# boost-converter.net
KiCad netlist of a schematic drawn in Altium Designer
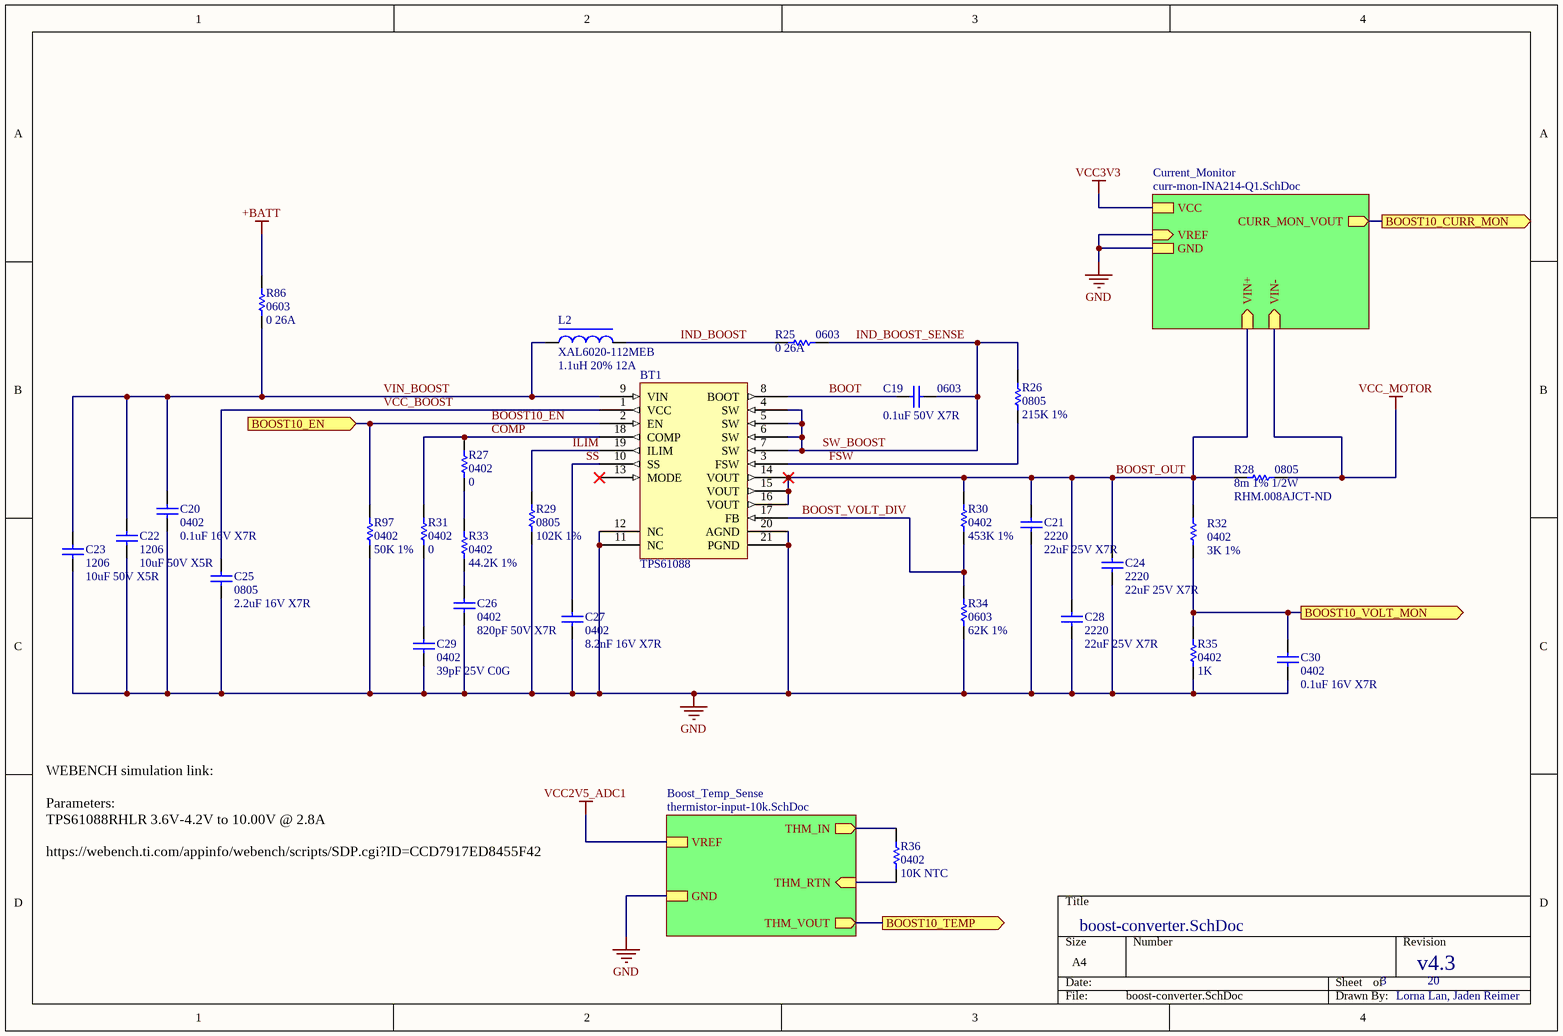
[diagram p0: boost-converter.SchDoc]

(export (version "E")
  (design (tool "Eeschema 10.0.6"))
  (components
    (comp (ref "BT1")
      (value "TPS61088")
      (footprint "QFN50P450X350X100-21N")
      (description "Boost converter")
      (libsource (lib "EPS") (part "TPS61088"))
    )
    (comp (ref "C19")
      (value "0603")
      (footprint "CAP0603R")
      (description "0603 capacitor")
      (fields (field (name "ALTIUM_VALUE") "0.1uF 50V X7R"))
      (libsource (lib "CAP0603") (part "CAP0603"))
    )
    (comp (ref "C20")
      (value "0402")
      (footprint "CAP0402R")
      (description "0402 capacitor")
      (fields (field (name "ALTIUM_VALUE") "0.1uF 16V X7R"))
      (libsource (lib "heron-general") (part "CAP0402"))
    )
    (comp (ref "C21")
      (value "2220")
      (footprint "CAP2220")
      (description "Ceramic Capacitor 2220 (5750 Metric)")
      (fields (field (name "ALTIUM_VALUE") "22uF 25V X7R"))
      (libsource (lib "CAP2220") (part "CAP2220"))
    )
    (comp (ref "C22")
      (value "1206")
      (footprint "CAP1206R")
      (description "1206 capacitor")
      (fields (field (name "ALTIUM_VALUE") "10uF 50V X5R"))
      (libsource (lib "CAP1206") (part "CAP1206"))
    )
    (comp (ref "C23")
      (value "1206")
      (footprint "CAP1206R")
      (description "1206 capacitor")
      (fields (field (name "ALTIUM_VALUE") "10uF 50V X5R"))
      (libsource (lib "CAP1206") (part "CAP1206"))
    )
    (comp (ref "C24")
      (value "2220")
      (footprint "CAP2220")
      (description "Ceramic Capacitor 2220 (5750 Metric)")
      (fields (field (name "ALTIUM_VALUE") "22uF 25V X7R"))
      (libsource (lib "CAP2220") (part "CAP2220"))
    )
    (comp (ref "C25")
      (value "0805")
      (footprint "CAP0805R")
      (description "0805 capacitor")
      (fields (field (name "ALTIUM_VALUE") "2.2uF 16V X7R"))
      (libsource (lib "heron-general") (part "CAP0805"))
    )
    (comp (ref "C26")
      (value "0402")
      (footprint "CAP0402R")
      (description "0402 capacitor")
      (fields (field (name "ALTIUM_VALUE") "820pF 50V X7R"))
      (libsource (lib "CAP0402") (part "CAP0402"))
    )
    (comp (ref "C27")
      (value "0402")
      (footprint "CAP0402R")
      (description "0402 capacitor")
      (fields (field (name "ALTIUM_VALUE") "8.2nF 16V X7R"))
      (libsource (lib "CAP0402") (part "CAP0402"))
    )
    (comp (ref "C28")
      (value "2220")
      (footprint "CAP2220")
      (description "Ceramic Capacitor 2220 (5750 Metric)")
      (fields (field (name "ALTIUM_VALUE") "22uF 25V X7R"))
      (libsource (lib "CAP2220") (part "CAP2220"))
    )
    (comp (ref "C29")
      (value "0402")
      (footprint "CAP0402R")
      (description "0402 capacitor")
      (fields (field (name "ALTIUM_VALUE") "39pF 25V C0G"))
      (libsource (lib "CAP0402") (part "CAP0402"))
    )
    (comp (ref "C30")
      (value "0402")
      (footprint "CAP0402R")
      (description "0402 capacitor")
      (fields (field (name "ALTIUM_VALUE") "0.1uF 16V X7R"))
      (libsource (lib "heron-general") (part "CAP0402"))
    )
    (comp (ref "L2")
      (value "XAL6020-112MEB")
      (footprint "XAL6020-112MEB")
      (description "Fixed Inductors 1.1uH 20% 12A, 13.1mOhms AEC-Q200")
      (fields (field (name "ALTIUM_VALUE") "1.1uH 20% 12A"))
      (libsource (lib "heron-general") (part "XAL6020-112MEB"))
    )
    (comp (ref "R25")
      (value "0603")
      (footprint "RES0603R")
      (description "0603 resistor")
      (fields (field (name "ALTIUM_VALUE") "0 26A"))
      (libsource (lib "heron-general") (part "RES0603"))
    )
    (comp (ref "R26")
      (value "0805")
      (footprint "RES0805R")
      (description "0805 resistor")
      (fields (field (name "ALTIUM_VALUE") "215K 1%"))
      (libsource (lib "RES0805") (part "RES0805"))
    )
    (comp (ref "R27")
      (value "0402")
      (footprint "RES0402R")
      (description "0402 resistor")
      (fields
        (field (name "ALTIUM_VALUE") "0")
        (field (name "MANUFACTURER") "Panasonic")
        (field (name "MANUFACTURER PART NUMBER") "ERJ-2GE0R00X")
      )
      (libsource (lib "heron-general") (part "RES0402"))
    )
    (comp (ref "R28")
      (value "0805")
      (footprint "RES0805R")
      (description "0805 resistor")
      (fields
        (field (name "ALTIUM_VALUE") "8m 1% 1/2W")
        (field (name "SUPPLIER PART NUMBER 1") "RHM.008AJCT-ND")
      )
      (libsource (lib "RES0805") (part "RES0805"))
    )
    (comp (ref "R29")
      (value "0805")
      (footprint "RES0805R")
      (description "0805 resistor")
      (fields (field (name "ALTIUM_VALUE") "102K 1%"))
      (libsource (lib "RES0805") (part "RES0805"))
    )
    (comp (ref "R30")
      (value "0402")
      (footprint "RES0402R")
      (description "0402 resistor")
      (fields (field (name "ALTIUM_VALUE") "453K 1%"))
      (libsource (lib "RES0402") (part "RES0402"))
    )
    (comp (ref "R31")
      (value "0402")
      (footprint "RES0402R")
      (description "0402 resistor")
      (fields
        (field (name "ALTIUM_VALUE") "0")
        (field (name "MANUFACTURER") "Panasonic")
        (field (name "MANUFACTURER PART NUMBER") "ERJ-2GE0R00X")
      )
      (libsource (lib "heron-general") (part "RES0402"))
    )
    (comp (ref "R32")
      (value "0402")
      (footprint "RES0402R")
      (description "0402 resistor")
      (fields (field (name "ALTIUM_VALUE") "3K 1%"))
      (libsource (lib "RES0402") (part "RES0402"))
    )
    (comp (ref "R33")
      (value "0402")
      (footprint "RES0402R")
      (description "0402 resistor")
      (fields (field (name "ALTIUM_VALUE") "44.2K 1%"))
      (libsource (lib "heron-general") (part "RES0402"))
    )
    (comp (ref "R34")
      (value "0603")
      (footprint "RES0603R")
      (description "0603 resistor")
      (fields (field (name "ALTIUM_VALUE") "62K 1%"))
      (libsource (lib "RES0603") (part "RES0603"))
    )
    (comp (ref "R35")
      (value "0402")
      (footprint "RES0402R")
      (description "0402 resistor")
      (fields (field (name "ALTIUM_VALUE") "1K"))
      (libsource (lib "RES0402") (part "RES0402"))
    )
    (comp (ref "R36")
      (value "0402")
      (footprint "RES0402R")
      (description "0402 resistor")
      (fields (field (name "ALTIUM_VALUE") "10K NTC"))
      (libsource (lib "heron-general") (part "RES0402"))
    )
    (comp (ref "R86")
      (value "0603")
      (footprint "RES0603R")
      (description "0603 resistor")
      (fields (field (name "ALTIUM_VALUE") "0 26A"))
      (libsource (lib "heron-general") (part "RES0603"))
    )
    (comp (ref "R97")
      (value "0402")
      (footprint "RES0402R")
      (description "0402 resistor")
      (fields (field (name "ALTIUM_VALUE") "50K 1%"))
      (libsource (lib "heron-general") (part "RES0402"))
    )
  )
  (nets
    (net (code "1") (name "+BATT") (class "Default")
      (node (ref "R86") (pin "2") (pinfunction "2_2") (pintype "passive"))
    )
    (net (code "3") (name "/BOOST10_EN") (class "Default")
      (node (ref "BT1") (pin "2") (pinfunction "EN_2") (pintype "input"))
      (node (ref "R97") (pin "2") (pinfunction "2_2") (pintype "passive"))
    )
    (net (code "5") (name "/BOOST10_VOLT_MON") (class "Default")
      (node (ref "C30") (pin "2") (pinfunction "2_2") (pintype "passive"))
      (node (ref "R32") (pin "1") (pinfunction "1_1") (pintype "passive"))
      (node (ref "R35") (pin "2") (pinfunction "2_2") (pintype "passive"))
    )
    (net (code "6") (name "/BOOST_OUT") (class "Default")
      (node (ref "BT1") (pin "14") (pinfunction "VOUT_14") (pintype "output"))
      (node (ref "BT1") (pin "15") (pinfunction "VOUT_15") (pintype "output"))
      (node (ref "BT1") (pin "16") (pinfunction "VOUT_16") (pintype "output"))
      (node (ref "C21") (pin "2") (pinfunction "2_2") (pintype "passive"))
      (node (ref "C24") (pin "2") (pinfunction "2_2") (pintype "passive"))
      (node (ref "C28") (pin "2") (pinfunction "2_2") (pintype "passive"))
      (node (ref "R28") (pin "1") (pinfunction "1_1") (pintype "passive"))
      (node (ref "R30") (pin "2") (pinfunction "2_2") (pintype "passive"))
      (node (ref "R32") (pin "2") (pinfunction "2_2") (pintype "passive"))
    )
    (net (code "7") (name "/BOOST_VOLT_DIV") (class "Default")
      (node (ref "BT1") (pin "17") (pinfunction "FB_17") (pintype "input"))
      (node (ref "R30") (pin "1") (pinfunction "1_1") (pintype "passive"))
      (node (ref "R34") (pin "2") (pinfunction "2_2") (pintype "passive"))
    )
    (net (code "8") (name "/BOOT") (class "Default")
      (node (ref "BT1") (pin "8") (pinfunction "BOOT_8") (pintype "output"))
      (node (ref "C19") (pin "1") (pinfunction "1_1") (pintype "passive"))
    )
    (net (code "9") (name "/COMP") (class "Default")
      (node (ref "BT1") (pin "18") (pinfunction "COMP_18") (pintype "output"))
      (node (ref "R27") (pin "2") (pinfunction "2_2") (pintype "passive"))
      (node (ref "R31") (pin "2") (pinfunction "2_2") (pintype "passive"))
    )
    (net (code "10") (name "/FSW") (class "Default")
      (node (ref "BT1") (pin "3") (pinfunction "FSW_3") (pintype "input"))
      (node (ref "R26") (pin "1") (pinfunction "1_1") (pintype "passive"))
    )
    (net (code "11") (name "/ILIM") (class "Default")
      (node (ref "BT1") (pin "19") (pinfunction "ILIM_19") (pintype "output"))
      (node (ref "R29") (pin "2") (pinfunction "2_2") (pintype "passive"))
    )
    (net (code "12") (name "/IND_BOOST") (class "Default")
      (node (ref "L2") (pin "2") (pinfunction "2_2") (pintype "passive"))
      (node (ref "R25") (pin "1") (pinfunction "1_1") (pintype "passive"))
    )
    (net (code "13") (name "/IND_BOOST_SENSE") (class "Default")
      (node (ref "BT1") (pin "4") (pinfunction "SW_4") (pintype "input"))
      (node (ref "BT1") (pin "5") (pinfunction "SW_5") (pintype "input"))
      (node (ref "BT1") (pin "6") (pinfunction "SW_6") (pintype "input"))
      (node (ref "BT1") (pin "7") (pinfunction "SW_7") (pintype "input"))
      (node (ref "C19") (pin "2") (pinfunction "2_2") (pintype "passive"))
      (node (ref "R25") (pin "2") (pinfunction "2_2") (pintype "passive"))
      (node (ref "R26") (pin "2") (pinfunction "2_2") (pintype "passive"))
    )
    (net (code "14") (name "/SS") (class "Default")
      (node (ref "BT1") (pin "10") (pinfunction "SS_10") (pintype "output"))
      (node (ref "C27") (pin "2") (pinfunction "2_2") (pintype "passive"))
    )
    (net (code "15") (name "/THM_IN") (class "Default")
      (node (ref "R36") (pin "2") (pinfunction "2_2") (pintype "passive"))
    )
    (net (code "16") (name "/THM_RTN") (class "Default")
      (node (ref "R36") (pin "1") (pinfunction "1_1") (pintype "passive"))
    )
    (net (code "17") (name "/VCC_BOOST") (class "Default")
      (node (ref "BT1") (pin "1") (pinfunction "VCC_1") (pintype "output"))
      (node (ref "C25") (pin "2") (pinfunction "2_2") (pintype "passive"))
    )
    (net (code "18") (name "/VIN_BOOST") (class "Default")
      (node (ref "BT1") (pin "9") (pinfunction "VIN_9") (pintype "input"))
      (node (ref "C20") (pin "2") (pinfunction "2_2") (pintype "passive"))
      (node (ref "C22") (pin "2") (pinfunction "2_2") (pintype "passive"))
      (node (ref "C23") (pin "2") (pinfunction "2_2") (pintype "passive"))
      (node (ref "L2") (pin "1") (pinfunction "1_1") (pintype "passive"))
      (node (ref "R86") (pin "1") (pinfunction "1_1") (pintype "passive"))
    )
    (net (code "19") (name "GND") (class "Default")
      (node (ref "BT1") (pin "11") (pinfunction "NC_11") (pintype "passive"))
      (node (ref "BT1") (pin "12") (pinfunction "NC_12") (pintype "passive"))
      (node (ref "BT1") (pin "20") (pinfunction "AGND_20") (pintype "power_in"))
      (node (ref "BT1") (pin "21") (pinfunction "PGND_21") (pintype "power_in"))
      (node (ref "C20") (pin "1") (pinfunction "1_1") (pintype "passive"))
      (node (ref "C21") (pin "1") (pinfunction "1_1") (pintype "passive"))
      (node (ref "C22") (pin "1") (pinfunction "1_1") (pintype "passive"))
      (node (ref "C23") (pin "1") (pinfunction "1_1") (pintype "passive"))
      (node (ref "C24") (pin "1") (pinfunction "1_1") (pintype "passive"))
      (node (ref "C25") (pin "1") (pinfunction "1_1") (pintype "passive"))
      (node (ref "C26") (pin "1") (pinfunction "1_1") (pintype "passive"))
      (node (ref "C27") (pin "1") (pinfunction "1_1") (pintype "passive"))
      (node (ref "C28") (pin "1") (pinfunction "1_1") (pintype "passive"))
      (node (ref "C29") (pin "1") (pinfunction "1_1") (pintype "passive"))
      (node (ref "C30") (pin "1") (pinfunction "1_1") (pintype "passive"))
      (node (ref "R29") (pin "1") (pinfunction "1_1") (pintype "passive"))
      (node (ref "R34") (pin "1") (pinfunction "1_1") (pintype "passive"))
      (node (ref "R35") (pin "1") (pinfunction "1_1") (pintype "passive"))
      (node (ref "R97") (pin "1") (pinfunction "1_1") (pintype "passive"))
    )
    (net (code "20") (name "Net-(C26-Pad2)") (class "Default")
      (node (ref "C26") (pin "2") (pinfunction "2_2") (pintype "passive"))
      (node (ref "R33") (pin "1") (pinfunction "1_1") (pintype "passive"))
    )
    (net (code "21") (name "Net-(C29-Pad2)") (class "Default")
      (node (ref "C29") (pin "2") (pinfunction "2_2") (pintype "passive"))
      (node (ref "R31") (pin "1") (pinfunction "1_1") (pintype "passive"))
    )
    (net (code "22") (name "Net-(R27-Pad1)") (class "Default")
      (node (ref "R27") (pin "1") (pinfunction "1_1") (pintype "passive"))
      (node (ref "R33") (pin "2") (pinfunction "2_2") (pintype "passive"))
    )
    (net (code "25") (name "VCC_MOTOR") (class "Default")
      (node (ref "R28") (pin "2") (pinfunction "2_2") (pintype "passive"))
    )
    (net (code "26") (name "unconnected-(BT1-MODE-Pad13)") (class "Default")
      (node (ref "BT1") (pin "13") (pinfunction "MODE_13") (pintype "input+no_connect"))
    )
  )
)
